# TSAR_Actuator_Controller.net
KiCad netlist of a schematic drawn in EAGLE
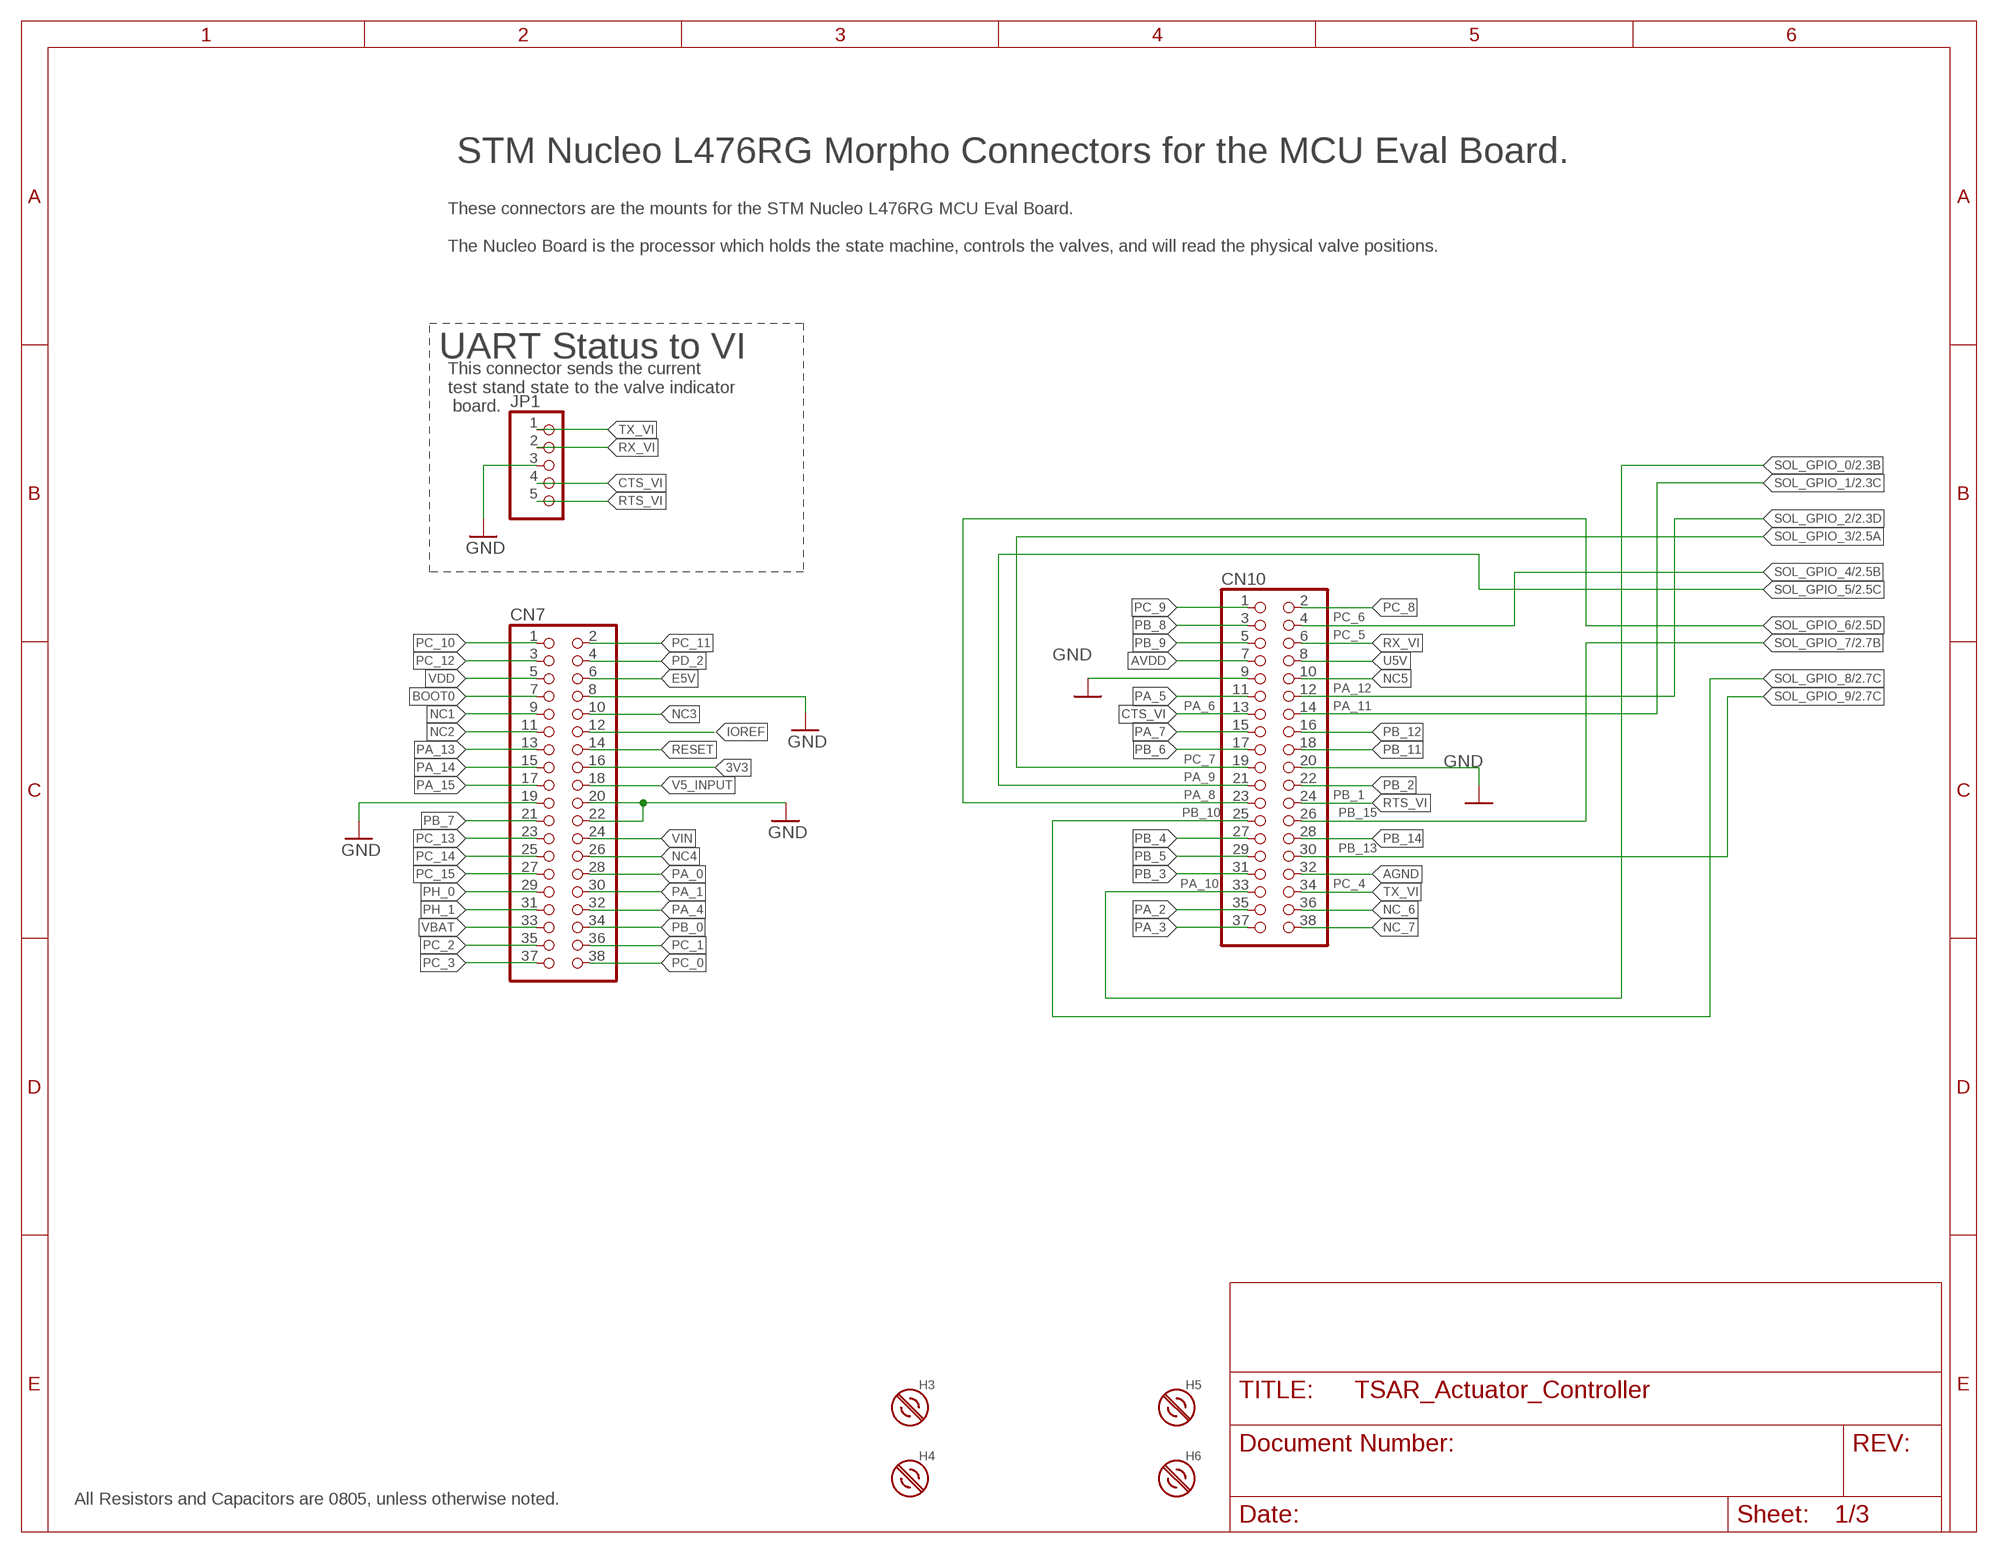
[diagram p0: schematic, sheet 1]
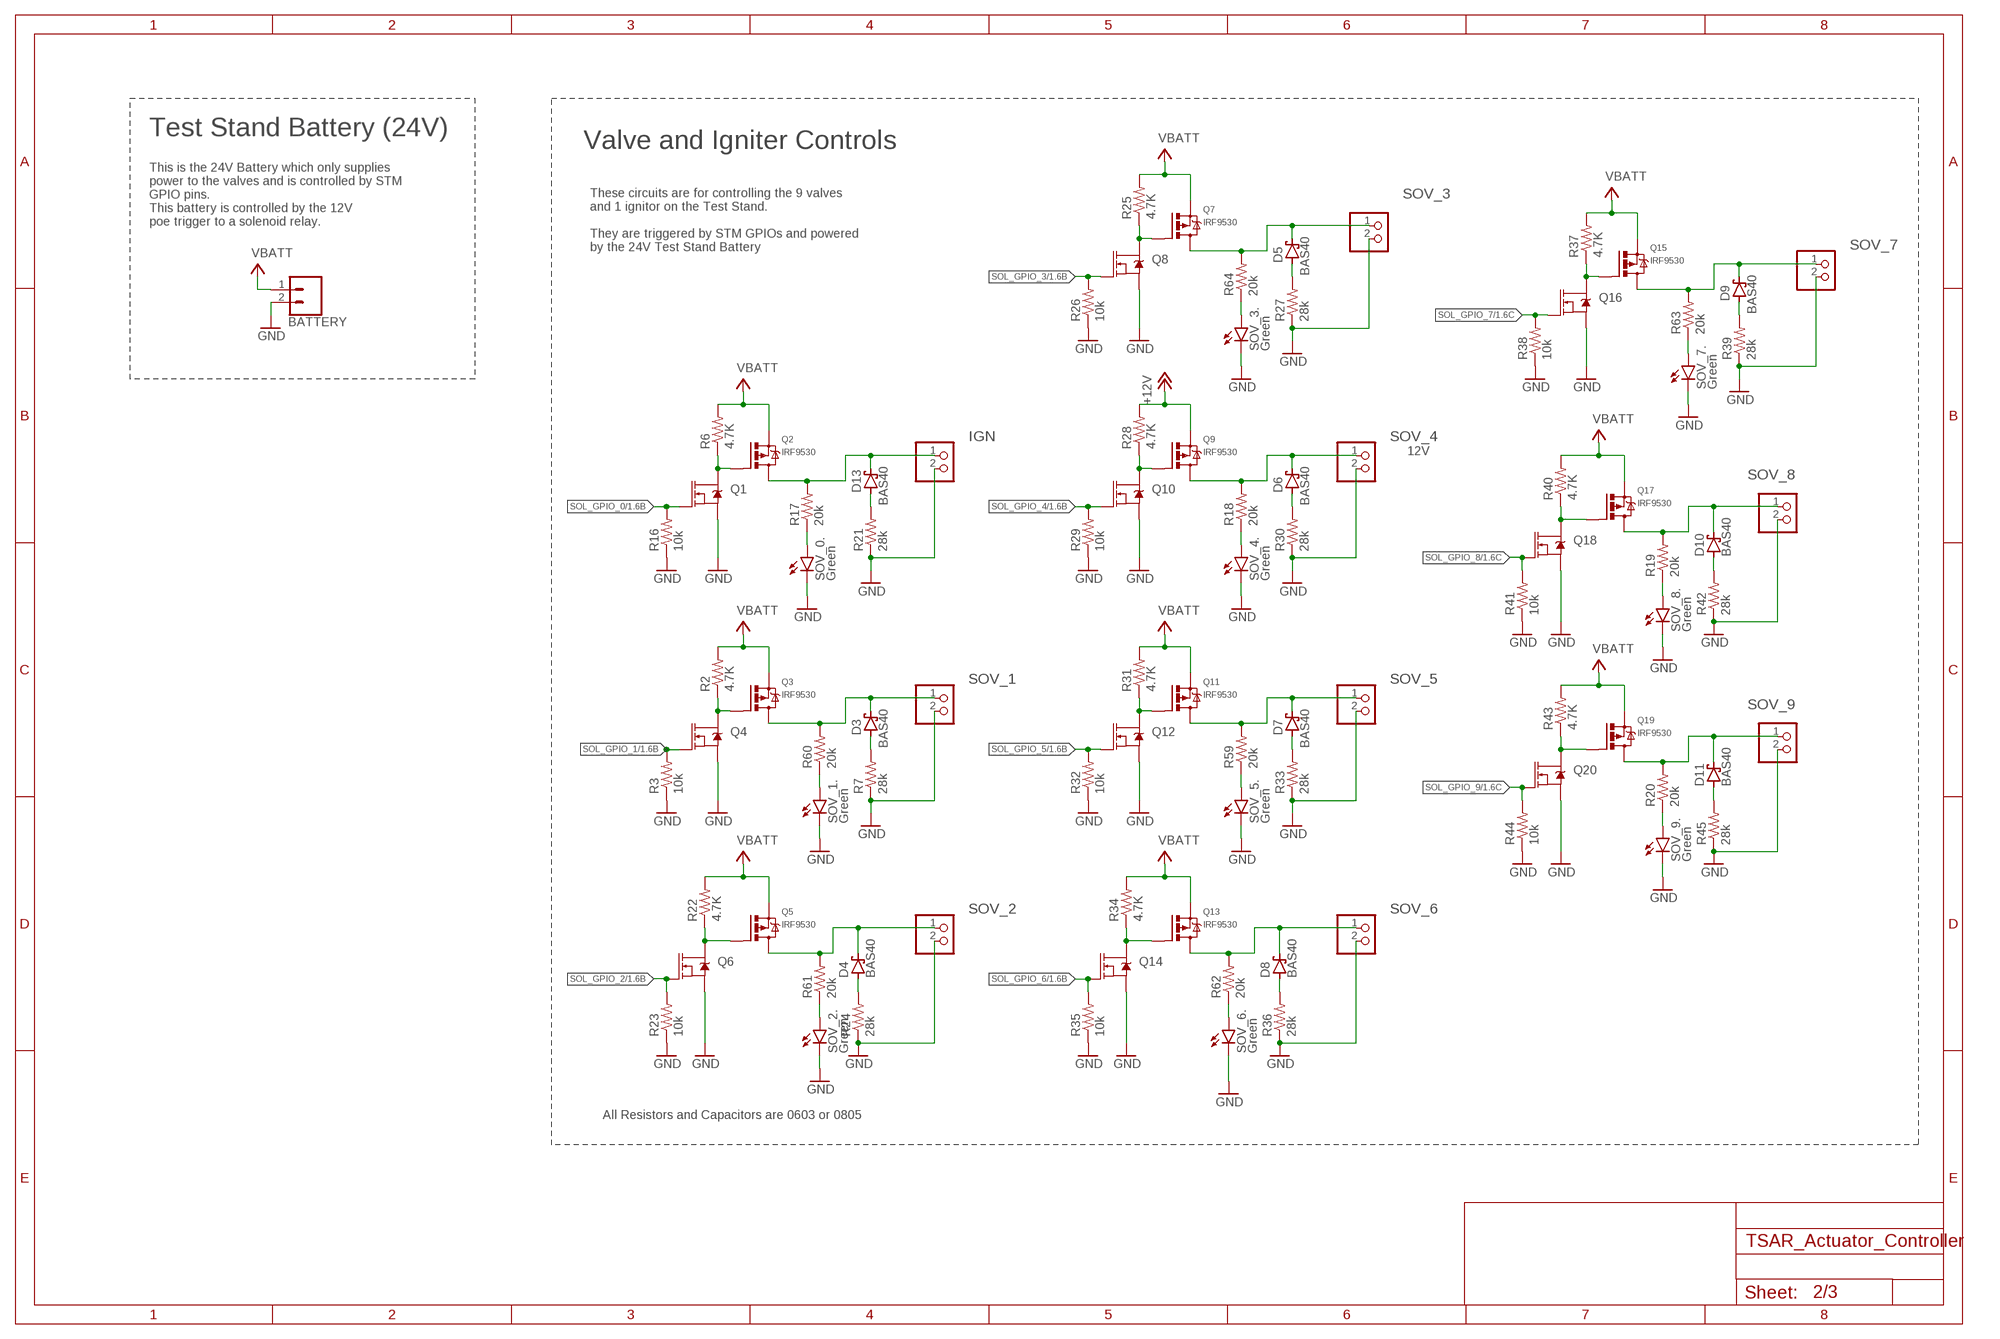
[diagram p1: schematic, sheet 2]
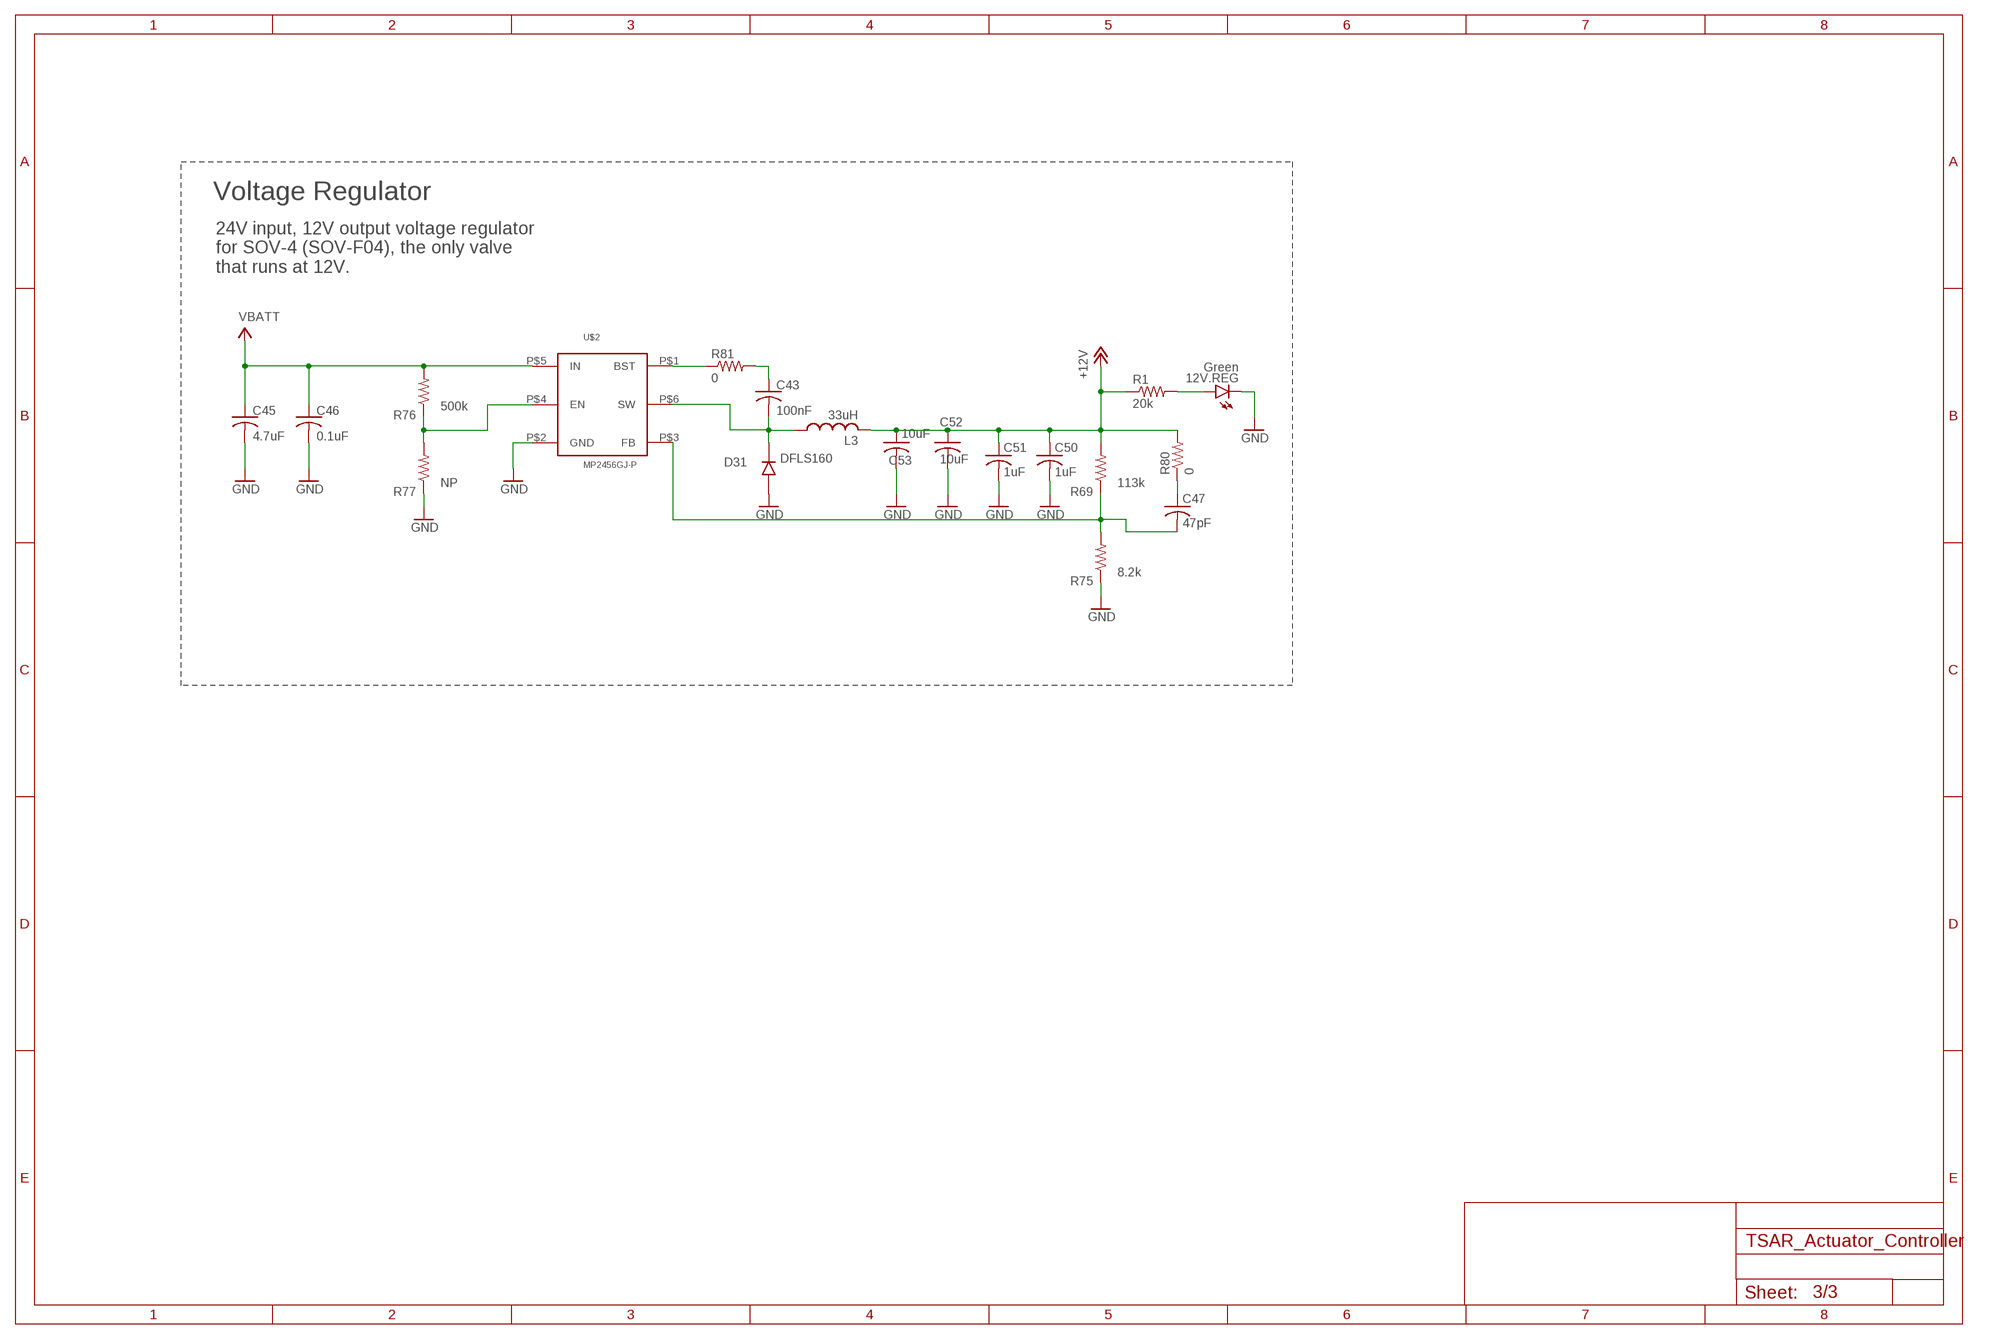
[diagram p2: schematic, sheet 3]

(export (version "E")
  (design (tool "Eeschema 10.0.6"))
  (components
    (comp (ref "12V.REG")
      (value "Green")
      (footprint "eagle-import:CHIP-LED0603")
      (fields (field (name "MFR") "Dialight") (field (name "MPN") "5988070107F"))
      (libsource (lib "eagle-import") (part "LEDCHIP-LED0603"))
    )
    (comp (ref "C43")
      (value "100nF")
      (footprint "eagle-import:C0603K")
      (fields (field (name "MFR") "Samsung Electro-Mechanics") (field (name "MPN") "CL10B104KB8NNNL"))
      (libsource (lib "eagle-import") (part "C-USC0603K"))
    )
    (comp (ref "C45")
      (value "4.7uF")
      (footprint "eagle-import:C0805K")
      (fields (field (name "MFR") "Samsung Electro-Mechanics") (field (name "MPN") "CL21A475KBQNNNE"))
      (libsource (lib "eagle-import") (part "C-USC0805K"))
    )
    (comp (ref "C46")
      (value "0.1uF")
      (footprint "eagle-import:C0603K")
      (fields (field (name "MFR") "Samsung Electro-Mechanics") (field (name "MPN") "CL10B104KB8NNNL"))
      (libsource (lib "eagle-import") (part "C-USC0603K"))
    )
    (comp (ref "C47")
      (value "47pF")
      (footprint "eagle-import:C0603K")
      (fields (field (name "MFR") "TDK Corporation") (field (name "MPN") "C1608C0G1H470J080AA"))
      (libsource (lib "eagle-import") (part "C-USC0603K"))
    )
    (comp (ref "C50")
      (value "1uF")
      (footprint "eagle-import:C0603K")
      (fields (field (name "MFR") "Samsung Electro-Mechanics") (field (name "MPN") "CL10A105KB8NNNC"))
      (libsource (lib "eagle-import") (part "C-USC0603K"))
    )
    (comp (ref "C51")
      (value "1uF")
      (footprint "eagle-import:C0603K")
      (fields (field (name "MFR") "Samsung Electro-Mechanics") (field (name "MPN") "CL10A105KB8NNNC"))
      (libsource (lib "eagle-import") (part "C-USC0603K"))
    )
    (comp (ref "C52")
      (value "10uF")
      (footprint "eagle-import:C1206K")
      (fields (field (name "MFR") "Samsung Electro-Mechanics") (field (name "MPN") "CL31A106MBHNNNE"))
      (libsource (lib "eagle-import") (part "C-USC1206K"))
    )
    (comp (ref "C53")
      (value "10uF")
      (footprint "eagle-import:C1206K")
      (fields (field (name "MFR") "Samsung Electro-Mechanics") (field (name "MPN") "CL31A106MBHNNNE"))
      (libsource (lib "eagle-import") (part "C-USC1206K"))
    )
    (comp (ref "D31")
      (value "DFLS160")
      (footprint "eagle-import:POWERDI-123")
      (fields
        (field (name "DIGI-KEY_PART_NUMBER") "DFLS160DICT-ND")
        (field (name "MF") "Diodes Inc.")
        (field (name "MP") "DFLS160-7")
      )
      (libsource (lib "eagle-import") (part "DFLS160-7"))
    )
    (comp (ref "L3")
      (value "33uH")
      (footprint "eagle-import:0.209_LX0.197_W(5.30MMX5.00MM)")
      (fields (field (name "MFR") "Pulse Electronics Power") (field (name "MPN") "PM4340.333NLT"))
      (libsource (lib "eagle-import") (part "CLF5030NIT-100M-D"))
    )
    (comp (ref "R1")
      (value "20k")
      (footprint "eagle-import:.0603-A-NOSILK")
      (fields (field (name "MFR") "Panasonic Electronic Components") (field (name "MPN") "ERJ-PA3J203V"))
      (libsource (lib "eagle-import") (part "R-US_0603-A-NOSILK"))
    )
    (comp (ref "R69")
      (value "113k")
      (footprint "eagle-import:.0805-A-NOSILK")
      (fields (field (name "MFR") "KOA Speer Electronics, Inc.") (field (name "MPN") "RK73H2ATTD1133F"))
      (libsource (lib "eagle-import") (part "R-US_0805-A-NOSILK"))
    )
    (comp (ref "R75")
      (value "8.2k")
      (footprint "eagle-import:.0805-A-NOSILK")
      (fields (field (name "MFR") "KOA Speer Electronics, Inc.") (field (name "MPN") "RK73H2ATTD8201F"))
      (libsource (lib "eagle-import") (part "R-US_0805-A-NOSILK"))
    )
    (comp (ref "R76")
      (value "500k")
      (footprint "eagle-import:1206-A")
      (fields (field (name "MFR") "Vishay Dale") (field (name "MPN") "CRMA1206AF500KFKEF"))
      (libsource (lib "eagle-import") (part "R-US_1206-A"))
    )
    (comp (ref "R77")
      (value "NP")
      (footprint "eagle-import:.0805-A-NOSILK")
      (libsource (lib "eagle-import") (part "R-US_0805-A-NOSILK"))
    )
    (comp (ref "R80")
      (value "0")
      (footprint "eagle-import:.0603-A-NOSILK")
      (fields (field (name "MFR") "Vishay Dale") (field (name "MPN") "RCS06030000Z0EA"))
      (libsource (lib "eagle-import") (part "R-US_0603-A-NOSILK"))
    )
    (comp (ref "R81")
      (value "0")
      (footprint "eagle-import:.0603-A-NOSILK")
      (fields (field (name "MFR") "Vishay Dale") (field (name "MPN") "RCS06030000Z0EA"))
      (libsource (lib "eagle-import") (part "R-US_0603-A-NOSILK"))
    )
    (comp (ref "U$2")
      (value "MP2456GJ-P")
      (footprint "eagle-import:SOT6")
      (fields (field (name "MFR") "Monolithic Power Systems Inc."))
      (libsource (lib "eagle-import") (part "MP2456GJ-P"))
    )
    (comp (ref "CN7")
      (value "PINHD-2X19")
      (footprint "eagle-import:2X19")
      (fields (field (name "MFR") "Sullins Connector Solutions") (field (name "MPN") "PPPC192LFBN-RC"))
      (libsource (lib "eagle-import") (part "PINHD-2X19"))
    )
    (comp (ref "CN10")
      (value "PINHD-2X19")
      (footprint "eagle-import:2X19")
      (fields (field (name "MFR") "Sullins Connector Solutions") (field (name "MPN") "PPPC192LFBN-RC"))
      (libsource (lib "eagle-import") (part "PINHD-2X19"))
    )
    (comp (ref "H3")
      (value "#4-BARE_MOUNTING_HOLE/.300")
      (footprint "eagle-import:#4_.300-BARE+STD_NUT_OR_STAR_WASHER")
      (libsource (lib "eagle-import") (part "#4-BARE_MOUNTING_HOLE/.300"))
    )
    (comp (ref "H4")
      (value "#4-BARE_MOUNTING_HOLE/.300")
      (footprint "eagle-import:#4_.300-BARE+STD_NUT_OR_STAR_WASHER")
      (libsource (lib "eagle-import") (part "#4-BARE_MOUNTING_HOLE/.300"))
    )
    (comp (ref "H5")
      (value "#4-BARE_MOUNTING_HOLE/.300")
      (footprint "eagle-import:#4_.300-BARE+STD_NUT_OR_STAR_WASHER")
      (libsource (lib "eagle-import") (part "#4-BARE_MOUNTING_HOLE/.300"))
    )
    (comp (ref "H6")
      (value "#4-BARE_MOUNTING_HOLE/.300")
      (footprint "eagle-import:#4_.300-BARE+STD_NUT_OR_STAR_WASHER")
      (libsource (lib "eagle-import") (part "#4-BARE_MOUNTING_HOLE/.300"))
    )
    (comp (ref "JP1")
      (value "PINHD-1X5")
      (footprint "eagle-import:1X05")
      (fields (field (name "MFR") "Molex") (field (name "MPN") "AWHW 10A-0202-T"))
      (libsource (lib "eagle-import") (part "PINHD-1X5"))
    )
    (comp (ref "BATTERY")
      (value "CONN_02PTH4")
      (footprint "eagle-import:1X02_XTRA_BIG")
      (fields (field (name "MFR") "TE Connectivity AMP Connectors") (field (name "MPN") "282837-2"))
      (libsource (lib "eagle-import") (part "CONN_02PTH4"))
    )
    (comp (ref "D3")
      (value "BAS40")
      (footprint "eagle-import:SOT23")
      (fields (field (name "MFR") "Central Semiconductor Corp") (field (name "MPN") "CMPSH1-4 TR PBFREE"))
      (libsource (lib "eagle-import") (part "BAS40"))
    )
    (comp (ref "D4")
      (value "BAS40")
      (footprint "eagle-import:SOT23")
      (fields (field (name "MFR") "Central Semiconductor Corp") (field (name "MPN") "CMPSH1-4 TR PBFREE"))
      (libsource (lib "eagle-import") (part "BAS40"))
    )
    (comp (ref "D5")
      (value "BAS40")
      (footprint "eagle-import:SOT23")
      (fields (field (name "MFR") "Central Semiconductor Corp") (field (name "MPN") "CMPSH1-4 TR PBFREE"))
      (libsource (lib "eagle-import") (part "BAS40"))
    )
    (comp (ref "D6")
      (value "BAS40")
      (footprint "eagle-import:SOT23")
      (fields (field (name "MFR") "Central Semiconductor Corp") (field (name "MPN") "CMPSH1-4 TR PBFREE"))
      (libsource (lib "eagle-import") (part "BAS40"))
    )
    (comp (ref "D7")
      (value "BAS40")
      (footprint "eagle-import:SOT23")
      (fields (field (name "MFR") "Central Semiconductor Corp") (field (name "MPN") "CMPSH1-4 TR PBFREE"))
      (libsource (lib "eagle-import") (part "BAS40"))
    )
    (comp (ref "D8")
      (value "BAS40")
      (footprint "eagle-import:SOT23")
      (fields (field (name "MFR") "Central Semiconductor Corp") (field (name "MPN") "CMPSH1-4 TR PBFREE"))
      (libsource (lib "eagle-import") (part "BAS40"))
    )
    (comp (ref "D9")
      (value "BAS40")
      (footprint "eagle-import:SOT23")
      (fields (field (name "MFR") "Central Semiconductor Corp") (field (name "MPN") "CMPSH1-4 TR PBFREE"))
      (libsource (lib "eagle-import") (part "BAS40"))
    )
    (comp (ref "D10")
      (value "BAS40")
      (footprint "eagle-import:SOT23")
      (fields (field (name "MFR") "Central Semiconductor Corp") (field (name "MPN") "CMPSH1-4 TR PBFREE"))
      (libsource (lib "eagle-import") (part "BAS40"))
    )
    (comp (ref "D11")
      (value "BAS40")
      (footprint "eagle-import:SOT23")
      (fields (field (name "MFR") "Central Semiconductor Corp") (field (name "MPN") "CMPSH1-4 TR PBFREE"))
      (libsource (lib "eagle-import") (part "BAS40"))
    )
    (comp (ref "D13")
      (value "BAS40")
      (footprint "eagle-import:SOT23")
      (fields (field (name "MFR") "Central Semiconductor Corp") (field (name "MPN") "CMPSH1-4 TR PBFREE"))
      (libsource (lib "eagle-import") (part "BAS40"))
    )
    (comp (ref "IGN")
      (value "PINHD-1X2")
      (footprint "eagle-import:1X02")
      (fields (field (name "MFR") "Molex") (field (name "MPN") "0022232021"))
      (libsource (lib "eagle-import") (part "PINHD-1X2"))
    )
    (comp (ref "Q1")
      (value "220mA/50V/3.5Ω")
      (footprint "eagle-import:SOT23-3")
      (fields (field (name "MFR") "Nexperia USA Inc.") (field (name "MPN") "BSS138P,215"))
      (libsource (lib "eagle-import") (part "MOSFET-NCH-BSS138"))
    )
    (comp (ref "Q2")
      (value "IRF9530")
      (footprint "eagle-import:TO220BV")
      (fields (field (name "MFR") "Infineon Technologies") (field (name "MPN") "IRF9530NPBF"))
      (libsource (lib "eagle-import") (part "IRF9530"))
    )
    (comp (ref "Q3")
      (value "IRF9530")
      (footprint "eagle-import:TO220BV")
      (fields (field (name "MFR") "Infineon Technologies") (field (name "MPN") "IRF9530NPBF"))
      (libsource (lib "eagle-import") (part "IRF9530"))
    )
    (comp (ref "Q4")
      (value "220mA/50V/3.5Ω")
      (footprint "eagle-import:SOT23-3")
      (fields (field (name "MFR") "Nexperia USA Inc.") (field (name "MPN") "BSS138P,215"))
      (libsource (lib "eagle-import") (part "MOSFET-NCH-BSS138"))
    )
    (comp (ref "Q5")
      (value "IRF9530")
      (footprint "eagle-import:TO220BV")
      (fields (field (name "MFR") "Infineon Technologies") (field (name "MPN") "IRF9530NPBF"))
      (libsource (lib "eagle-import") (part "IRF9530"))
    )
    (comp (ref "Q6")
      (value "220mA/50V/3.5Ω")
      (footprint "eagle-import:SOT23-3")
      (fields (field (name "MFR") "Nexperia USA Inc.") (field (name "MPN") "BSS138P,215"))
      (libsource (lib "eagle-import") (part "MOSFET-NCH-BSS138"))
    )
    (comp (ref "Q7")
      (value "IRF9530")
      (footprint "eagle-import:TO220BV")
      (fields (field (name "MFR") "Infineon Technologies") (field (name "MPN") "IRF9530NPBF"))
      (libsource (lib "eagle-import") (part "IRF9530"))
    )
    (comp (ref "Q8")
      (value "220mA/50V/3.5Ω")
      (footprint "eagle-import:SOT23-3")
      (fields (field (name "MFR") "Nexperia USA Inc.") (field (name "MPN") "BSS138P,215"))
      (libsource (lib "eagle-import") (part "MOSFET-NCH-BSS138"))
    )
    (comp (ref "Q9")
      (value "IRF9530")
      (footprint "eagle-import:TO220BV")
      (fields (field (name "MFR") "Infineon Technologies") (field (name "MPN") "IRF9530NPBF"))
      (libsource (lib "eagle-import") (part "IRF9530"))
    )
    (comp (ref "Q10")
      (value "220mA/50V/3.5Ω")
      (footprint "eagle-import:SOT23-3")
      (fields (field (name "MFR") "Nexperia USA Inc.") (field (name "MPN") "BSS138P,215"))
      (libsource (lib "eagle-import") (part "MOSFET-NCH-BSS138"))
    )
    (comp (ref "Q11")
      (value "IRF9530")
      (footprint "eagle-import:TO220BV")
      (fields (field (name "MFR") "Infineon Technologies") (field (name "MPN") "IRF9530NPBF"))
      (libsource (lib "eagle-import") (part "IRF9530"))
    )
    (comp (ref "Q12")
      (value "220mA/50V/3.5Ω")
      (footprint "eagle-import:SOT23-3")
      (fields (field (name "MFR") "Nexperia USA Inc.") (field (name "MPN") "BSS138P,215"))
      (libsource (lib "eagle-import") (part "MOSFET-NCH-BSS138"))
    )
    (comp (ref "Q13")
      (value "IRF9530")
      (footprint "eagle-import:TO220BV")
      (fields (field (name "MFR") "Infineon Technologies") (field (name "MPN") "IRF9530NPBF"))
      (libsource (lib "eagle-import") (part "IRF9530"))
    )
    (comp (ref "Q14")
      (value "220mA/50V/3.5Ω")
      (footprint "eagle-import:SOT23-3")
      (fields (field (name "MFR") "Nexperia USA Inc.") (field (name "MPN") "BSS138P,215"))
      (libsource (lib "eagle-import") (part "MOSFET-NCH-BSS138"))
    )
    (comp (ref "Q15")
      (value "IRF9530")
      (footprint "eagle-import:TO220BV")
      (fields (field (name "MFR") "Infineon Technologies") (field (name "MPN") "IRF9530NPBF"))
      (libsource (lib "eagle-import") (part "IRF9530"))
    )
    (comp (ref "Q16")
      (value "220mA/50V/3.5Ω")
      (footprint "eagle-import:SOT23-3")
      (fields (field (name "MFR") "Nexperia USA Inc.") (field (name "MPN") "BSS138P,215"))
      (libsource (lib "eagle-import") (part "MOSFET-NCH-BSS138"))
    )
    (comp (ref "Q17")
      (value "IRF9530")
      (footprint "eagle-import:TO220BV")
      (fields (field (name "MFR") "Infineon Technologies") (field (name "MPN") "IRF9530NPBF"))
      (libsource (lib "eagle-import") (part "IRF9530"))
    )
    (comp (ref "Q18")
      (value "220mA/50V/3.5Ω")
      (footprint "eagle-import:SOT23-3")
      (fields (field (name "MFR") "Nexperia USA Inc.") (field (name "MPN") "BSS138P,215"))
      (libsource (lib "eagle-import") (part "MOSFET-NCH-BSS138"))
    )
    (comp (ref "Q19")
      (value "IRF9530")
      (footprint "eagle-import:TO220BV")
      (fields (field (name "MFR") "Infineon Technologies") (field (name "MPN") "IRF9530NPBF"))
      (libsource (lib "eagle-import") (part "IRF9530"))
    )
    (comp (ref "Q20")
      (value "220mA/50V/3.5Ω")
      (footprint "eagle-import:SOT23-3")
      (fields (field (name "MFR") "Nexperia USA Inc.") (field (name "MPN") "BSS138P,215"))
      (libsource (lib "eagle-import") (part "MOSFET-NCH-BSS138"))
    )
    (comp (ref "R2")
      (value "4.7K")
      (footprint "eagle-import:.0805-A-NOSILK")
      (fields (field (name "MFR") "Yageo") (field (name "MPN") "RC0805FR-074K7L"))
      (libsource (lib "eagle-import") (part "R-US_0805-A-NOSILK"))
    )
    (comp (ref "R3")
      (value "10k")
      (footprint "eagle-import:.0805-A-NOSILK")
      (fields (field (name "MFR") "Yageo") (field (name "MPN") "RC0805FR-0710KL"))
      (libsource (lib "eagle-import") (part "R-US_0805-A-NOSILK"))
    )
    (comp (ref "R6")
      (value "4.7K")
      (footprint "eagle-import:.0805-A-NOSILK")
      (fields (field (name "MFR") "Yageo") (field (name "MPN") "RC0805FR-074K7L"))
      (libsource (lib "eagle-import") (part "R-US_0805-A-NOSILK"))
    )
    (comp (ref "R7")
      (value "28k")
      (footprint "eagle-import:.0805-A-NOSILK")
      (fields (field (name "MFR") "Stackpole Electronics Inc") (field (name "MPN") "RMCF0805FT28K0"))
      (libsource (lib "eagle-import") (part "R-US_0805-A-NOSILK"))
    )
    (comp (ref "R16")
      (value "10k")
      (footprint "eagle-import:.0805-A-NOSILK")
      (fields (field (name "MFR") "Yageo") (field (name "MPN") "RC0805FR-0710KL"))
      (libsource (lib "eagle-import") (part "R-US_0805-A-NOSILK"))
    )
    (comp (ref "R17")
      (value "20k")
      (footprint "eagle-import:.0603-A-NOSILK")
      (fields (field (name "MFR") "Rohm Semiconductor") (field (name "MPN") "ESR03EZPJ203"))
      (libsource (lib "eagle-import") (part "R-US_0603-A-NOSILK"))
    )
    (comp (ref "R18")
      (value "20k")
      (footprint "eagle-import:.0603-A-NOSILK")
      (fields (field (name "MFR") "Rohm Semiconductor") (field (name "MPN") "ESR03EZPJ203"))
      (libsource (lib "eagle-import") (part "R-US_0603-A-NOSILK"))
    )
    (comp (ref "R19")
      (value "20k")
      (footprint "eagle-import:.0603-A-NOSILK")
      (fields (field (name "MFR") "Rohm Semiconductor") (field (name "MPN") "ESR03EZPJ203"))
      (libsource (lib "eagle-import") (part "R-US_0603-A-NOSILK"))
    )
    (comp (ref "R20")
      (value "20k")
      (footprint "eagle-import:.0603-A-NOSILK")
      (fields (field (name "MFR") "Rohm Semiconductor") (field (name "MPN") "ESR03EZPJ203"))
      (libsource (lib "eagle-import") (part "R-US_0603-A-NOSILK"))
    )
    (comp (ref "R21")
      (value "28k")
      (footprint "eagle-import:.0805-A-NOSILK")
      (fields (field (name "MFR") "Stackpole Electronics Inc") (field (name "MPN") "RMCF0805FT28K0"))
      (libsource (lib "eagle-import") (part "R-US_0805-A-NOSILK"))
    )
    (comp (ref "R22")
      (value "4.7K")
      (footprint "eagle-import:.0805-A-NOSILK")
      (fields (field (name "MFR") "Yageo") (field (name "MPN") "RC0805FR-074K7L"))
      (libsource (lib "eagle-import") (part "R-US_0805-A-NOSILK"))
    )
    (comp (ref "R23")
      (value "10k")
      (footprint "eagle-import:.0805-A-NOSILK")
      (fields (field (name "MFR") "Yageo") (field (name "MPN") "RC0805FR-0710KL"))
      (libsource (lib "eagle-import") (part "R-US_0805-A-NOSILK"))
    )
    (comp (ref "R24")
      (value "28k")
      (footprint "eagle-import:.0805-A-NOSILK")
      (fields (field (name "MFR") "Stackpole Electronics Inc") (field (name "MPN") "RMCF0805FT28K0"))
      (libsource (lib "eagle-import") (part "R-US_0805-A-NOSILK"))
    )
    (comp (ref "R25")
      (value "4.7K")
      (footprint "eagle-import:.0805-A-NOSILK")
      (fields (field (name "MFR") "Yageo") (field (name "MPN") "RC0805FR-074K7L"))
      (libsource (lib "eagle-import") (part "R-US_0805-A-NOSILK"))
    )
    (comp (ref "R26")
      (value "10k")
      (footprint "eagle-import:.0805-A-NOSILK")
      (fields (field (name "MFR") "Yageo") (field (name "MPN") "RC0805FR-0710KL"))
      (libsource (lib "eagle-import") (part "R-US_0805-A-NOSILK"))
    )
    (comp (ref "R27")
      (value "28k")
      (footprint "eagle-import:.0805-A-NOSILK")
      (fields (field (name "MFR") "Stackpole Electronics Inc") (field (name "MPN") "RMCF0805FT28K0"))
      (libsource (lib "eagle-import") (part "R-US_0805-A-NOSILK"))
    )
    (comp (ref "R28")
      (value "4.7K")
      (footprint "eagle-import:.0805-A-NOSILK")
      (fields (field (name "MFR") "Yageo") (field (name "MPN") "RC0805FR-074K7L"))
      (libsource (lib "eagle-import") (part "R-US_0805-A-NOSILK"))
    )
    (comp (ref "R29")
      (value "10k")
      (footprint "eagle-import:.0805-A-NOSILK")
      (fields (field (name "MFR") "Yageo") (field (name "MPN") "RC0805FR-0710KL"))
      (libsource (lib "eagle-import") (part "R-US_0805-A-NOSILK"))
    )
    (comp (ref "R30")
      (value "28k")
      (footprint "eagle-import:.0805-A-NOSILK")
      (fields (field (name "MFR") "Stackpole Electronics Inc") (field (name "MPN") "RMCF0805FT28K0"))
      (libsource (lib "eagle-import") (part "R-US_0805-A-NOSILK"))
    )
    (comp (ref "R31")
      (value "4.7K")
      (footprint "eagle-import:.0805-A-NOSILK")
      (fields (field (name "MFR") "Yageo") (field (name "MPN") "RC0805FR-074K7L"))
      (libsource (lib "eagle-import") (part "R-US_0805-A-NOSILK"))
    )
    (comp (ref "R32")
      (value "10k")
      (footprint "eagle-import:.0805-A-NOSILK")
      (fields (field (name "MFR") "Yageo") (field (name "MPN") "RC0805FR-0710KL"))
      (libsource (lib "eagle-import") (part "R-US_0805-A-NOSILK"))
    )
    (comp (ref "R33")
      (value "28k")
      (footprint "eagle-import:.0805-A-NOSILK")
      (fields (field (name "MFR") "Stackpole Electronics Inc") (field (name "MPN") "RMCF0805FT28K0"))
      (libsource (lib "eagle-import") (part "R-US_0805-A-NOSILK"))
    )
    (comp (ref "R34")
      (value "4.7K")
      (footprint "eagle-import:.0805-A-NOSILK")
      (fields (field (name "MFR") "Yageo") (field (name "MPN") "RC0805FR-074K7L"))
      (libsource (lib "eagle-import") (part "R-US_0805-A-NOSILK"))
    )
    (comp (ref "R35")
      (value "10k")
      (footprint "eagle-import:.0805-A-NOSILK")
      (fields (field (name "MFR") "Yageo") (field (name "MPN") "RC0805FR-0710KL"))
      (libsource (lib "eagle-import") (part "R-US_0805-A-NOSILK"))
    )
    (comp (ref "R36")
      (value "28k")
      (footprint "eagle-import:.0805-A-NOSILK")
      (fields (field (name "MFR") "Stackpole Electronics Inc") (field (name "MPN") "RMCF0805FT28K0"))
      (libsource (lib "eagle-import") (part "R-US_0805-A-NOSILK"))
    )
    (comp (ref "R37")
      (value "4.7K")
      (footprint "eagle-import:.0805-A-NOSILK")
      (fields (field (name "MFR") "Yageo") (field (name "MPN") "RC0805FR-074K7L"))
      (libsource (lib "eagle-import") (part "R-US_0805-A-NOSILK"))
    )
    (comp (ref "R38")
      (value "10k")
      (footprint "eagle-import:.0805-A-NOSILK")
      (fields (field (name "MFR") "Yageo") (field (name "MPN") "RC0805FR-0710KL"))
      (libsource (lib "eagle-import") (part "R-US_0805-A-NOSILK"))
    )
    (comp (ref "R39")
      (value "28k")
      (footprint "eagle-import:.0805-A-NOSILK")
      (fields (field (name "MFR") "Stackpole Electronics Inc") (field (name "MPN") "RMCF0805FT28K0"))
      (libsource (lib "eagle-import") (part "R-US_0805-A-NOSILK"))
    )
    (comp (ref "R40")
      (value "4.7K")
      (footprint "eagle-import:.0805-A-NOSILK")
      (fields (field (name "MFR") "Yageo") (field (name "MPN") "RC0805FR-074K7L"))
      (libsource (lib "eagle-import") (part "R-US_0805-A-NOSILK"))
    )
    (comp (ref "R41")
      (value "10k")
      (footprint "eagle-import:.0805-A-NOSILK")
      (fields (field (name "MFR") "Yageo") (field (name "MPN") "RC0805FR-0710KL"))
      (libsource (lib "eagle-import") (part "R-US_0805-A-NOSILK"))
    )
    (comp (ref "R42")
      (value "28k")
      (footprint "eagle-import:.0805-A-NOSILK")
      (fields (field (name "MFR") "Stackpole Electronics Inc") (field (name "MPN") "RMCF0805FT28K0"))
      (libsource (lib "eagle-import") (part "R-US_0805-A-NOSILK"))
    )
    (comp (ref "R43")
      (value "4.7K")
      (footprint "eagle-import:.0805-A-NOSILK")
      (fields (field (name "MFR") "Yageo") (field (name "MPN") "RC0805FR-074K7L"))
      (libsource (lib "eagle-import") (part "R-US_0805-A-NOSILK"))
    )
    (comp (ref "R44")
      (value "10k")
      (footprint "eagle-import:.0805-A-NOSILK")
      (fields (field (name "MFR") "Yageo") (field (name "MPN") "RC0805FR-0710KL"))
      (libsource (lib "eagle-import") (part "R-US_0805-A-NOSILK"))
    )
    (comp (ref "R45")
      (value "28k")
      (footprint "eagle-import:.0805-A-NOSILK")
      (fields (field (name "MFR") "Stackpole Electronics Inc") (field (name "MPN") "RMCF0805FT28K0"))
      (libsource (lib "eagle-import") (part "R-US_0805-A-NOSILK"))
    )
    (comp (ref "R59")
      (value "20k")
      (footprint "eagle-import:.0603-A-NOSILK")
      (fields (field (name "MFR") "Rohm Semiconductor") (field (name "MPN") "ESR03EZPJ203"))
      (libsource (lib "eagle-import") (part "R-US_0603-A-NOSILK"))
    )
    (comp (ref "R60")
      (value "20k")
      (footprint "eagle-import:.0603-A-NOSILK")
      (fields (field (name "MFR") "Rohm Semiconductor") (field (name "MPN") "ESR03EZPJ203"))
      (libsource (lib "eagle-import") (part "R-US_0603-A-NOSILK"))
    )
    (comp (ref "R61")
      (value "20k")
      (footprint "eagle-import:.0603-A-NOSILK")
      (fields (field (name "MFR") "Rohm Semiconductor") (field (name "MPN") "ESR03EZPJ203"))
      (libsource (lib "eagle-import") (part "R-US_0603-A-NOSILK"))
    )
    (comp (ref "R62")
      (value "20k")
      (footprint "eagle-import:.0603-A-NOSILK")
      (fields (field (name "MFR") "Rohm Semiconductor") (field (name "MPN") "ESR03EZPJ203"))
      (libsource (lib "eagle-import") (part "R-US_0603-A-NOSILK"))
    )
    (comp (ref "R63")
      (value "20k")
      (footprint "eagle-import:.0603-A-NOSILK")
      (fields (field (name "MFR") "Rohm Semiconductor") (field (name "MPN") "ESR03EZPJ203"))
      (libsource (lib "eagle-import") (part "R-US_0603-A-NOSILK"))
    )
    (comp (ref "R64")
      (value "20k")
      (footprint "eagle-import:.0603-A-NOSILK")
      (fields (field (name "MFR") "Rohm Semiconductor") (field (name "MPN") "ESR03EZPJ203"))
      (libsource (lib "eagle-import") (part "R-US_0603-A-NOSILK"))
    )
    (comp (ref "SOV_0.")
      (value "Green")
      (footprint "eagle-import:CHIP-LED0603")
      (fields (field (name "MFR") "Dialight") (field (name "MPN") "5988070107F"))
      (libsource (lib "eagle-import") (part "LEDCHIP-LED0603"))
    )
    (comp (ref "SOV_1")
      (value "PINHD-1X2")
      (footprint "eagle-import:1X02")
      (fields (field (name "MFR") "Molex") (field (name "MPN") "0022232021"))
      (libsource (lib "eagle-import") (part "PINHD-1X2"))
    )
    (comp (ref "SOV_1.")
      (value "Green")
      (footprint "eagle-import:CHIP-LED0603")
      (fields (field (name "MFR") "Dialight") (field (name "MPN") "5988070107F"))
      (libsource (lib "eagle-import") (part "LEDCHIP-LED0603"))
    )
    (comp (ref "SOV_2")
      (value "PINHD-1X2")
      (footprint "eagle-import:1X02")
      (fields (field (name "MFR") "Molex") (field (name "MPN") "0022232021"))
      (libsource (lib "eagle-import") (part "PINHD-1X2"))
    )
    (comp (ref "SOV_2.")
      (value "Green")
      (footprint "eagle-import:CHIP-LED0603")
      (fields (field (name "MFR") "Dialight") (field (name "MPN") "5988070107F"))
      (libsource (lib "eagle-import") (part "LEDCHIP-LED0603"))
    )
    (comp (ref "SOV_3")
      (value "PINHD-1X2")
      (footprint "eagle-import:1X02")
      (fields (field (name "MFR") "Molex") (field (name "MPN") "0022232021"))
      (libsource (lib "eagle-import") (part "PINHD-1X2"))
    )
    (comp (ref "SOV_3.")
      (value "Green")
      (footprint "eagle-import:CHIP-LED0603")
      (fields (field (name "MFR") "Dialight") (field (name "MPN") "5988070107F"))
      (libsource (lib "eagle-import") (part "LEDCHIP-LED0603"))
    )
    (comp (ref "SOV_4")
      (value "PINHD-1X2")
      (footprint "eagle-import:1X02")
      (fields (field (name "MFR") "Molex") (field (name "MPN") "0022232021"))
      (libsource (lib "eagle-import") (part "PINHD-1X2"))
    )
    (comp (ref "SOV_4.")
      (value "Green")
      (footprint "eagle-import:CHIP-LED0603")
      (fields (field (name "MFR") "Dialight") (field (name "MPN") "5988070107F"))
      (libsource (lib "eagle-import") (part "LEDCHIP-LED0603"))
    )
    (comp (ref "SOV_5")
      (value "PINHD-1X2")
      (footprint "eagle-import:1X02")
      (fields (field (name "MFR") "Molex") (field (name "MPN") "0022232021"))
      (libsource (lib "eagle-import") (part "PINHD-1X2"))
    )
    (comp (ref "SOV_5.")
      (value "Green")
      (footprint "eagle-import:CHIP-LED0603")
      (fields (field (name "MFR") "Dialight") (field (name "MPN") "5988070107F"))
      (libsource (lib "eagle-import") (part "LEDCHIP-LED0603"))
    )
    (comp (ref "SOV_6")
      (value "PINHD-1X2")
      (footprint "eagle-import:1X02")
      (fields (field (name "MFR") "Molex") (field (name "MPN") "0022232021"))
      (libsource (lib "eagle-import") (part "PINHD-1X2"))
    )
    (comp (ref "SOV_6.")
      (value "Green")
      (footprint "eagle-import:CHIP-LED0603")
      (fields (field (name "MFR") "Dialight") (field (name "MPN") "5988070107F"))
      (libsource (lib "eagle-import") (part "LEDCHIP-LED0603"))
    )
    (comp (ref "SOV_7")
      (value "PINHD-1X2")
      (footprint "eagle-import:1X02")
      (fields (field (name "MFR") "Molex") (field (name "MPN") "0022232021"))
      (libsource (lib "eagle-import") (part "PINHD-1X2"))
    )
    (comp (ref "SOV_7.")
      (value "Green")
      (footprint "eagle-import:CHIP-LED0603")
      (fields (field (name "MFR") "Dialight") (field (name "MPN") "5988070107F"))
      (libsource (lib "eagle-import") (part "LEDCHIP-LED0603"))
    )
    (comp (ref "SOV_8")
      (value "PINHD-1X2")
      (footprint "eagle-import:1X02")
      (fields (field (name "MFR") "Molex") (field (name "MPN") "0022232021"))
      (libsource (lib "eagle-import") (part "PINHD-1X2"))
    )
    (comp (ref "SOV_8.")
      (value "Green")
      (footprint "eagle-import:CHIP-LED0603")
      (fields (field (name "MFR") "Dialight") (field (name "MPN") "5988070107F"))
      (libsource (lib "eagle-import") (part "LEDCHIP-LED0603"))
    )
    (comp (ref "SOV_9")
      (value "PINHD-1X2")
      (footprint "eagle-import:1X02")
      (fields (field (name "MFR") "Molex") (field (name "MPN") "0022232021"))
      (libsource (lib "eagle-import") (part "PINHD-1X2"))
    )
    (comp (ref "SOV_9.")
      (value "Green")
      (footprint "eagle-import:CHIP-LED0603")
      (fields (field (name "MFR") "Dialight") (field (name "MPN") "5988070107F"))
      (libsource (lib "eagle-import") (part "LEDCHIP-LED0603"))
    )
  )
  (nets
    (net (code "1") (name "+12V") (class "Default")
      (node (ref "C50") (pin "1") (pinfunction "1_1") (pintype "passive"))
      (node (ref "C51") (pin "1") (pinfunction "1_1") (pintype "passive"))
      (node (ref "C52") (pin "1") (pinfunction "1_1") (pintype "passive"))
      (node (ref "C53") (pin "1") (pinfunction "1_1") (pintype "passive"))
      (node (ref "L3") (pin "2") (pinfunction "2_2") (pintype "passive"))
      (node (ref "Q9") (pin "S") (pinfunction "S_S") (pintype "passive"))
      (node (ref "R1") (pin "1") (pinfunction "1_1") (pintype "passive"))
      (node (ref "R28") (pin "2") (pinfunction "2_2") (pintype "passive"))
      (node (ref "R69") (pin "2") (pinfunction "2_2") (pintype "passive"))
      (node (ref "R80") (pin "2") (pinfunction "2_2") (pintype "passive"))
    )
    (net (code "2") (name "3V3") (class "Default")
      (node (ref "CN7") (pin "16") (pinfunction "16_16") (pintype "passive"))
    )
    (net (code "3") (name "AGND") (class "Default")
      (node (ref "CN10") (pin "32") (pinfunction "32_32") (pintype "passive"))
    )
    (net (code "4") (name "AVDD") (class "Default")
      (node (ref "CN10") (pin "7") (pinfunction "7_7") (pintype "passive"))
    )
    (net (code "5") (name "BOOT0") (class "Default")
      (node (ref "CN7") (pin "7") (pinfunction "7_7") (pintype "passive"))
    )
    (net (code "6") (name "CTS_VI") (class "Default")
      (node (ref "CN10") (pin "13") (pinfunction "13_13") (pintype "passive"))
      (node (ref "JP1") (pin "4") (pinfunction "4_4") (pintype "passive"))
    )
    (net (code "7") (name "E5V") (class "Default")
      (node (ref "CN7") (pin "6") (pinfunction "6_6") (pintype "passive"))
    )
    (net (code "8") (name "GND") (class "Default")
      (node (ref "12V.REG") (pin "C") (pinfunction "C_C") (pintype "passive"))
      (node (ref "BATTERY") (pin "2") (pinfunction "2_2") (pintype "passive"))
      (node (ref "C45") (pin "2") (pinfunction "2_2") (pintype "passive"))
      (node (ref "C46") (pin "2") (pinfunction "2_2") (pintype "passive"))
      (node (ref "C50") (pin "2") (pinfunction "2_2") (pintype "passive"))
      (node (ref "C51") (pin "2") (pinfunction "2_2") (pintype "passive"))
      (node (ref "C52") (pin "2") (pinfunction "2_2") (pintype "passive"))
      (node (ref "C53") (pin "2") (pinfunction "2_2") (pintype "passive"))
      (node (ref "CN10") (pin "20") (pinfunction "20_20") (pintype "passive"))
      (node (ref "CN10") (pin "9") (pinfunction "9_9") (pintype "passive"))
      (node (ref "CN7") (pin "19") (pinfunction "19_19") (pintype "passive"))
      (node (ref "CN7") (pin "20") (pinfunction "20_20") (pintype "passive"))
      (node (ref "CN7") (pin "22") (pinfunction "22_22") (pintype "passive"))
      (node (ref "CN7") (pin "8") (pinfunction "8_8") (pintype "passive"))
      (node (ref "D31") (pin "A") (pinfunction "A_A") (pintype "passive"))
      (node (ref "IGN") (pin "2") (pinfunction "2_2") (pintype "passive"))
      (node (ref "JP1") (pin "3") (pinfunction "3_3") (pintype "passive"))
      (node (ref "Q1") (pin "2") (pinfunction "S_2") (pintype "bidirectional"))
      (node (ref "Q10") (pin "2") (pinfunction "S_2") (pintype "bidirectional"))
      (node (ref "Q12") (pin "2") (pinfunction "S_2") (pintype "bidirectional"))
      (node (ref "Q14") (pin "2") (pinfunction "S_2") (pintype "bidirectional"))
      (node (ref "Q16") (pin "2") (pinfunction "S_2") (pintype "bidirectional"))
      (node (ref "Q18") (pin "2") (pinfunction "S_2") (pintype "bidirectional"))
      (node (ref "Q20") (pin "2") (pinfunction "S_2") (pintype "bidirectional"))
      (node (ref "Q4") (pin "2") (pinfunction "S_2") (pintype "bidirectional"))
      (node (ref "Q6") (pin "2") (pinfunction "S_2") (pintype "bidirectional"))
      (node (ref "Q8") (pin "2") (pinfunction "S_2") (pintype "bidirectional"))
      (node (ref "R16") (pin "1") (pinfunction "1_1") (pintype "passive"))
      (node (ref "R21") (pin "1") (pinfunction "1_1") (pintype "passive"))
      (node (ref "R23") (pin "1") (pinfunction "1_1") (pintype "passive"))
      (node (ref "R24") (pin "1") (pinfunction "1_1") (pintype "passive"))
      (node (ref "R26") (pin "1") (pinfunction "1_1") (pintype "passive"))
      (node (ref "R27") (pin "1") (pinfunction "1_1") (pintype "passive"))
      (node (ref "R29") (pin "1") (pinfunction "1_1") (pintype "passive"))
      (node (ref "R3") (pin "1") (pinfunction "1_1") (pintype "passive"))
      (node (ref "R30") (pin "1") (pinfunction "1_1") (pintype "passive"))
      (node (ref "R32") (pin "1") (pinfunction "1_1") (pintype "passive"))
      (node (ref "R33") (pin "1") (pinfunction "1_1") (pintype "passive"))
      (node (ref "R35") (pin "1") (pinfunction "1_1") (pintype "passive"))
      (node (ref "R36") (pin "1") (pinfunction "1_1") (pintype "passive"))
      (node (ref "R38") (pin "1") (pinfunction "1_1") (pintype "passive"))
      (node (ref "R39") (pin "1") (pinfunction "1_1") (pintype "passive"))
      (node (ref "R41") (pin "1") (pinfunction "1_1") (pintype "passive"))
      (node (ref "R42") (pin "1") (pinfunction "1_1") (pintype "passive"))
      (node (ref "R44") (pin "1") (pinfunction "1_1") (pintype "passive"))
      (node (ref "R45") (pin "1") (pinfunction "1_1") (pintype "passive"))
      (node (ref "R7") (pin "1") (pinfunction "1_1") (pintype "passive"))
      (node (ref "R75") (pin "1") (pinfunction "1_1") (pintype "passive"))
      (node (ref "R77") (pin "1") (pinfunction "1_1") (pintype "passive"))
      (node (ref "SOV_0.") (pin "C") (pinfunction "C_C") (pintype "passive"))
      (node (ref "SOV_1") (pin "2") (pinfunction "2_2") (pintype "passive"))
      (node (ref "SOV_1.") (pin "C") (pinfunction "C_C") (pintype "passive"))
      (node (ref "SOV_2") (pin "2") (pinfunction "2_2") (pintype "passive"))
      (node (ref "SOV_2.") (pin "C") (pinfunction "C_C") (pintype "passive"))
      (node (ref "SOV_3") (pin "2") (pinfunction "2_2") (pintype "passive"))
      (node (ref "SOV_3.") (pin "C") (pinfunction "C_C") (pintype "passive"))
      (node (ref "SOV_4") (pin "2") (pinfunction "2_2") (pintype "passive"))
      (node (ref "SOV_4.") (pin "C") (pinfunction "C_C") (pintype "passive"))
      (node (ref "SOV_5") (pin "2") (pinfunction "2_2") (pintype "passive"))
      (node (ref "SOV_5.") (pin "C") (pinfunction "C_C") (pintype "passive"))
      (node (ref "SOV_6") (pin "2") (pinfunction "2_2") (pintype "passive"))
      (node (ref "SOV_6.") (pin "C") (pinfunction "C_C") (pintype "passive"))
      (node (ref "SOV_7") (pin "2") (pinfunction "2_2") (pintype "passive"))
      (node (ref "SOV_7.") (pin "C") (pinfunction "C_C") (pintype "passive"))
      (node (ref "SOV_8") (pin "2") (pinfunction "2_2") (pintype "passive"))
      (node (ref "SOV_8.") (pin "C") (pinfunction "C_C") (pintype "passive"))
      (node (ref "SOV_9") (pin "2") (pinfunction "2_2") (pintype "passive"))
      (node (ref "SOV_9.") (pin "C") (pinfunction "C_C") (pintype "passive"))
      (node (ref "U$2") (pin "P$2") (pinfunction "GND_P$2") (pintype "bidirectional"))
    )
    (net (code "9") (name "IOREF") (class "Default")
      (node (ref "CN7") (pin "12") (pinfunction "12_12") (pintype "passive"))
    )
    (net (code "10") (name "NC1") (class "Default")
      (node (ref "CN7") (pin "9") (pinfunction "9_9") (pintype "passive"))
    )
    (net (code "11") (name "NC2") (class "Default")
      (node (ref "CN7") (pin "11") (pinfunction "11_11") (pintype "passive"))
    )
    (net (code "12") (name "NC3") (class "Default")
      (node (ref "CN7") (pin "10") (pinfunction "10_10") (pintype "passive"))
    )
    (net (code "13") (name "NC4") (class "Default")
      (node (ref "CN7") (pin "26") (pinfunction "26_26") (pintype "passive"))
    )
    (net (code "14") (name "NC5") (class "Default")
      (node (ref "CN10") (pin "10") (pinfunction "10_10") (pintype "passive"))
    )
    (net (code "15") (name "NC_6") (class "Default")
      (node (ref "CN10") (pin "36") (pinfunction "36_36") (pintype "passive"))
    )
    (net (code "16") (name "NC_7") (class "Default")
      (node (ref "CN10") (pin "38") (pinfunction "38_38") (pintype "passive"))
    )
    (net (code "17") (name "Net-(12V.REG-PadA)") (class "Default")
      (node (ref "12V.REG") (pin "A") (pinfunction "A_A") (pintype "passive"))
      (node (ref "R1") (pin "2") (pinfunction "2_2") (pintype "passive"))
    )
    (net (code "18") (name "Net-(C43-Pad1)") (class "Default")
      (node (ref "C43") (pin "1") (pinfunction "1_1") (pintype "passive"))
      (node (ref "R81") (pin "2") (pinfunction "2_2") (pintype "passive"))
    )
    (net (code "19") (name "Net-(C47-Pad1)") (class "Default")
      (node (ref "C47") (pin "1") (pinfunction "1_1") (pintype "passive"))
      (node (ref "R80") (pin "1") (pinfunction "1_1") (pintype "passive"))
    )
    (net (code "20") (name "Net-(D3-A)") (class "Default")
      (node (ref "D3") (pin "1") (pinfunction "A_1") (pintype "passive"))
      (node (ref "R7") (pin "2") (pinfunction "2_2") (pintype "passive"))
    )
    (net (code "21") (name "Net-(D3-C)") (class "Default")
      (node (ref "D3") (pin "3") (pinfunction "C_3") (pintype "passive"))
      (node (ref "Q3") (pin "D") (pinfunction "D_D") (pintype "passive"))
      (node (ref "R60") (pin "2") (pinfunction "2_2") (pintype "passive"))
      (node (ref "SOV_1") (pin "1") (pinfunction "1_1") (pintype "passive"))
    )
    (net (code "22") (name "Net-(D4-A)") (class "Default")
      (node (ref "D4") (pin "1") (pinfunction "A_1") (pintype "passive"))
      (node (ref "R24") (pin "2") (pinfunction "2_2") (pintype "passive"))
    )
    (net (code "23") (name "Net-(D4-C)") (class "Default")
      (node (ref "D4") (pin "3") (pinfunction "C_3") (pintype "passive"))
      (node (ref "Q5") (pin "D") (pinfunction "D_D") (pintype "passive"))
      (node (ref "R61") (pin "2") (pinfunction "2_2") (pintype "passive"))
      (node (ref "SOV_2") (pin "1") (pinfunction "1_1") (pintype "passive"))
    )
    (net (code "24") (name "Net-(D5-A)") (class "Default")
      (node (ref "D5") (pin "1") (pinfunction "A_1") (pintype "passive"))
      (node (ref "R27") (pin "2") (pinfunction "2_2") (pintype "passive"))
    )
    (net (code "25") (name "Net-(D5-C)") (class "Default")
      (node (ref "D5") (pin "3") (pinfunction "C_3") (pintype "passive"))
      (node (ref "Q7") (pin "D") (pinfunction "D_D") (pintype "passive"))
      (node (ref "R64") (pin "2") (pinfunction "2_2") (pintype "passive"))
      (node (ref "SOV_3") (pin "1") (pinfunction "1_1") (pintype "passive"))
    )
    (net (code "26") (name "Net-(D6-A)") (class "Default")
      (node (ref "D6") (pin "1") (pinfunction "A_1") (pintype "passive"))
      (node (ref "R30") (pin "2") (pinfunction "2_2") (pintype "passive"))
    )
    (net (code "27") (name "Net-(D6-C)") (class "Default")
      (node (ref "D6") (pin "3") (pinfunction "C_3") (pintype "passive"))
      (node (ref "Q9") (pin "D") (pinfunction "D_D") (pintype "passive"))
      (node (ref "R18") (pin "2") (pinfunction "2_2") (pintype "passive"))
      (node (ref "SOV_4") (pin "1") (pinfunction "1_1") (pintype "passive"))
    )
    (net (code "28") (name "Net-(D7-A)") (class "Default")
      (node (ref "D7") (pin "1") (pinfunction "A_1") (pintype "passive"))
      (node (ref "R33") (pin "2") (pinfunction "2_2") (pintype "passive"))
    )
    (net (code "29") (name "Net-(D7-C)") (class "Default")
      (node (ref "D7") (pin "3") (pinfunction "C_3") (pintype "passive"))
      (node (ref "Q11") (pin "D") (pinfunction "D_D") (pintype "passive"))
      (node (ref "R59") (pin "2") (pinfunction "2_2") (pintype "passive"))
      (node (ref "SOV_5") (pin "1") (pinfunction "1_1") (pintype "passive"))
    )
    (net (code "30") (name "Net-(D8-A)") (class "Default")
      (node (ref "D8") (pin "1") (pinfunction "A_1") (pintype "passive"))
      (node (ref "R36") (pin "2") (pinfunction "2_2") (pintype "passive"))
    )
    (net (code "31") (name "Net-(D8-C)") (class "Default")
      (node (ref "D8") (pin "3") (pinfunction "C_3") (pintype "passive"))
      (node (ref "Q13") (pin "D") (pinfunction "D_D") (pintype "passive"))
      (node (ref "R62") (pin "2") (pinfunction "2_2") (pintype "passive"))
      (node (ref "SOV_6") (pin "1") (pinfunction "1_1") (pintype "passive"))
    )
    (net (code "32") (name "Net-(D9-A)") (class "Default")
      (node (ref "D9") (pin "1") (pinfunction "A_1") (pintype "passive"))
      (node (ref "R39") (pin "2") (pinfunction "2_2") (pintype "passive"))
    )
    (net (code "33") (name "Net-(D9-C)") (class "Default")
      (node (ref "D9") (pin "3") (pinfunction "C_3") (pintype "passive"))
      (node (ref "Q15") (pin "D") (pinfunction "D_D") (pintype "passive"))
      (node (ref "R63") (pin "2") (pinfunction "2_2") (pintype "passive"))
      (node (ref "SOV_7") (pin "1") (pinfunction "1_1") (pintype "passive"))
    )
    (net (code "34") (name "Net-(D10-A)") (class "Default")
      (node (ref "D10") (pin "1") (pinfunction "A_1") (pintype "passive"))
      (node (ref "R42") (pin "2") (pinfunction "2_2") (pintype "passive"))
    )
    (net (code "35") (name "Net-(D10-C)") (class "Default")
      (node (ref "D10") (pin "3") (pinfunction "C_3") (pintype "passive"))
      (node (ref "Q17") (pin "D") (pinfunction "D_D") (pintype "passive"))
      (node (ref "R19") (pin "2") (pinfunction "2_2") (pintype "passive"))
      (node (ref "SOV_8") (pin "1") (pinfunction "1_1") (pintype "passive"))
    )
    (net (code "36") (name "Net-(D11-A)") (class "Default")
      (node (ref "D11") (pin "1") (pinfunction "A_1") (pintype "passive"))
      (node (ref "R45") (pin "2") (pinfunction "2_2") (pintype "passive"))
    )
    (net (code "37") (name "Net-(D11-C)") (class "Default")
      (node (ref "D11") (pin "3") (pinfunction "C_3") (pintype "passive"))
      (node (ref "Q19") (pin "D") (pinfunction "D_D") (pintype "passive"))
      (node (ref "R20") (pin "2") (pinfunction "2_2") (pintype "passive"))
      (node (ref "SOV_9") (pin "1") (pinfunction "1_1") (pintype "passive"))
    )
    (net (code "38") (name "Net-(D13-A)") (class "Default")
      (node (ref "D13") (pin "1") (pinfunction "A_1") (pintype "passive"))
      (node (ref "R21") (pin "2") (pinfunction "2_2") (pintype "passive"))
    )
    (net (code "39") (name "Net-(D13-C)") (class "Default")
      (node (ref "D13") (pin "3") (pinfunction "C_3") (pintype "passive"))
      (node (ref "IGN") (pin "1") (pinfunction "1_1") (pintype "passive"))
      (node (ref "Q2") (pin "D") (pinfunction "D_D") (pintype "passive"))
      (node (ref "R17") (pin "2") (pinfunction "2_2") (pintype "passive"))
    )
    (net (code "40") (name "Net-(Q1-D)") (class "Default")
      (node (ref "Q1") (pin "3") (pinfunction "D_3") (pintype "bidirectional"))
      (node (ref "Q2") (pin "G") (pinfunction "G_G") (pintype "passive"))
      (node (ref "R6") (pin "1") (pinfunction "1_1") (pintype "passive"))
    )
    (net (code "41") (name "Net-(Q4-D)") (class "Default")
      (node (ref "Q3") (pin "G") (pinfunction "G_G") (pintype "passive"))
      (node (ref "Q4") (pin "3") (pinfunction "D_3") (pintype "bidirectional"))
      (node (ref "R2") (pin "1") (pinfunction "1_1") (pintype "passive"))
    )
    (net (code "42") (name "Net-(Q6-D)") (class "Default")
      (node (ref "Q5") (pin "G") (pinfunction "G_G") (pintype "passive"))
      (node (ref "Q6") (pin "3") (pinfunction "D_3") (pintype "bidirectional"))
      (node (ref "R22") (pin "1") (pinfunction "1_1") (pintype "passive"))
    )
    (net (code "43") (name "Net-(Q8-D)") (class "Default")
      (node (ref "Q7") (pin "G") (pinfunction "G_G") (pintype "passive"))
      (node (ref "Q8") (pin "3") (pinfunction "D_3") (pintype "bidirectional"))
      (node (ref "R25") (pin "1") (pinfunction "1_1") (pintype "passive"))
    )
    (net (code "44") (name "Net-(Q10-D)") (class "Default")
      (node (ref "Q10") (pin "3") (pinfunction "D_3") (pintype "bidirectional"))
      (node (ref "Q9") (pin "G") (pinfunction "G_G") (pintype "passive"))
      (node (ref "R28") (pin "1") (pinfunction "1_1") (pintype "passive"))
    )
    (net (code "45") (name "Net-(Q12-D)") (class "Default")
      (node (ref "Q11") (pin "G") (pinfunction "G_G") (pintype "passive"))
      (node (ref "Q12") (pin "3") (pinfunction "D_3") (pintype "bidirectional"))
      (node (ref "R31") (pin "1") (pinfunction "1_1") (pintype "passive"))
    )
    (net (code "46") (name "Net-(Q14-D)") (class "Default")
      (node (ref "Q13") (pin "G") (pinfunction "G_G") (pintype "passive"))
      (node (ref "Q14") (pin "3") (pinfunction "D_3") (pintype "bidirectional"))
      (node (ref "R34") (pin "1") (pinfunction "1_1") (pintype "passive"))
    )
    (net (code "47") (name "Net-(Q16-D)") (class "Default")
      (node (ref "Q15") (pin "G") (pinfunction "G_G") (pintype "passive"))
      (node (ref "Q16") (pin "3") (pinfunction "D_3") (pintype "bidirectional"))
      (node (ref "R37") (pin "1") (pinfunction "1_1") (pintype "passive"))
    )
    (net (code "48") (name "Net-(Q18-D)") (class "Default")
      (node (ref "Q17") (pin "G") (pinfunction "G_G") (pintype "passive"))
      (node (ref "Q18") (pin "3") (pinfunction "D_3") (pintype "bidirectional"))
      (node (ref "R40") (pin "1") (pinfunction "1_1") (pintype "passive"))
    )
    (net (code "49") (name "Net-(Q20-D)") (class "Default")
      (node (ref "Q19") (pin "G") (pinfunction "G_G") (pintype "passive"))
      (node (ref "Q20") (pin "3") (pinfunction "D_3") (pintype "bidirectional"))
      (node (ref "R43") (pin "1") (pinfunction "1_1") (pintype "passive"))
    )
    (net (code "50") (name "Net-(R17-Pad1)") (class "Default")
      (node (ref "R17") (pin "1") (pinfunction "1_1") (pintype "passive"))
      (node (ref "SOV_0.") (pin "A") (pinfunction "A_A") (pintype "passive"))
    )
    (net (code "51") (name "Net-(R18-Pad1)") (class "Default")
      (node (ref "R18") (pin "1") (pinfunction "1_1") (pintype "passive"))
      (node (ref "SOV_4.") (pin "A") (pinfunction "A_A") (pintype "passive"))
    )
    (net (code "52") (name "Net-(R19-Pad1)") (class "Default")
      (node (ref "R19") (pin "1") (pinfunction "1_1") (pintype "passive"))
      (node (ref "SOV_8.") (pin "A") (pinfunction "A_A") (pintype "passive"))
    )
    (net (code "53") (name "Net-(R20-Pad1)") (class "Default")
      (node (ref "R20") (pin "1") (pinfunction "1_1") (pintype "passive"))
      (node (ref "SOV_9.") (pin "A") (pinfunction "A_A") (pintype "passive"))
    )
    (net (code "54") (name "Net-(R59-Pad1)") (class "Default")
      (node (ref "R59") (pin "1") (pinfunction "1_1") (pintype "passive"))
      (node (ref "SOV_5.") (pin "A") (pinfunction "A_A") (pintype "passive"))
    )
    (net (code "55") (name "Net-(R60-Pad1)") (class "Default")
      (node (ref "R60") (pin "1") (pinfunction "1_1") (pintype "passive"))
      (node (ref "SOV_1.") (pin "A") (pinfunction "A_A") (pintype "passive"))
    )
    (net (code "56") (name "Net-(R61-Pad1)") (class "Default")
      (node (ref "R61") (pin "1") (pinfunction "1_1") (pintype "passive"))
      (node (ref "SOV_2.") (pin "A") (pinfunction "A_A") (pintype "passive"))
    )
    (net (code "57") (name "Net-(R62-Pad1)") (class "Default")
      (node (ref "R62") (pin "1") (pinfunction "1_1") (pintype "passive"))
      (node (ref "SOV_6.") (pin "A") (pinfunction "A_A") (pintype "passive"))
    )
    (net (code "58") (name "Net-(R63-Pad1)") (class "Default")
      (node (ref "R63") (pin "1") (pinfunction "1_1") (pintype "passive"))
      (node (ref "SOV_7.") (pin "A") (pinfunction "A_A") (pintype "passive"))
    )
    (net (code "59") (name "Net-(R64-Pad1)") (class "Default")
      (node (ref "R64") (pin "1") (pinfunction "1_1") (pintype "passive"))
      (node (ref "SOV_3.") (pin "A") (pinfunction "A_A") (pintype "passive"))
    )
    (net (code "60") (name "Net-(U$2-BST)") (class "Default")
      (node (ref "R81") (pin "1") (pinfunction "1_1") (pintype "passive"))
      (node (ref "U$2") (pin "P$1") (pinfunction "BST_P$1") (pintype "bidirectional"))
    )
    (net (code "61") (name "Net-(U$2-EN)") (class "Default")
      (node (ref "R76") (pin "1") (pinfunction "1_1") (pintype "passive"))
      (node (ref "R77") (pin "2") (pinfunction "2_2") (pintype "passive"))
      (node (ref "U$2") (pin "P$4") (pinfunction "EN_P$4") (pintype "input"))
    )
    (net (code "62") (name "Net-(U$2-FB)") (class "Default")
      (node (ref "C47") (pin "2") (pinfunction "2_2") (pintype "passive"))
      (node (ref "R69") (pin "1") (pinfunction "1_1") (pintype "passive"))
      (node (ref "R75") (pin "2") (pinfunction "2_2") (pintype "passive"))
      (node (ref "U$2") (pin "P$3") (pinfunction "FB_P$3") (pintype "bidirectional"))
    )
    (net (code "63") (name "Net-(U$2-SW)") (class "Default")
      (node (ref "C43") (pin "2") (pinfunction "2_2") (pintype "passive"))
      (node (ref "D31") (pin "C") (pinfunction "C_C") (pintype "passive"))
      (node (ref "L3") (pin "1") (pinfunction "1_1") (pintype "passive"))
      (node (ref "U$2") (pin "P$6") (pinfunction "SW_P$6") (pintype "bidirectional"))
    )
    (net (code "64") (name "PA_0") (class "Default")
      (node (ref "CN7") (pin "28") (pinfunction "28_28") (pintype "passive"))
    )
    (net (code "65") (name "PA_1") (class "Default")
      (node (ref "CN7") (pin "30") (pinfunction "30_30") (pintype "passive"))
    )
    (net (code "66") (name "PA_2") (class "Default")
      (node (ref "CN10") (pin "35") (pinfunction "35_35") (pintype "passive"))
    )
    (net (code "67") (name "PA_3") (class "Default")
      (node (ref "CN10") (pin "37") (pinfunction "37_37") (pintype "passive"))
    )
    (net (code "68") (name "PA_4") (class "Default")
      (node (ref "CN7") (pin "32") (pinfunction "32_32") (pintype "passive"))
    )
    (net (code "69") (name "PA_5") (class "Default")
      (node (ref "CN10") (pin "11") (pinfunction "11_11") (pintype "passive"))
    )
    (net (code "70") (name "PA_7") (class "Default")
      (node (ref "CN10") (pin "15") (pinfunction "15_15") (pintype "passive"))
    )
    (net (code "71") (name "PA_13") (class "Default")
      (node (ref "CN7") (pin "13") (pinfunction "13_13") (pintype "passive"))
    )
    (net (code "72") (name "PA_14") (class "Default")
      (node (ref "CN7") (pin "15") (pinfunction "15_15") (pintype "passive"))
    )
    (net (code "73") (name "PA_15") (class "Default")
      (node (ref "CN7") (pin "17") (pinfunction "17_17") (pintype "passive"))
    )
    (net (code "74") (name "PB_0") (class "Default")
      (node (ref "CN7") (pin "34") (pinfunction "34_34") (pintype "passive"))
    )
    (net (code "75") (name "PB_2") (class "Default")
      (node (ref "CN10") (pin "22") (pinfunction "22_22") (pintype "passive"))
    )
    (net (code "76") (name "PB_3") (class "Default")
      (node (ref "CN10") (pin "31") (pinfunction "31_31") (pintype "passive"))
    )
    (net (code "77") (name "PB_4") (class "Default")
      (node (ref "CN10") (pin "27") (pinfunction "27_27") (pintype "passive"))
    )
    (net (code "78") (name "PB_5") (class "Default")
      (node (ref "CN10") (pin "29") (pinfunction "29_29") (pintype "passive"))
    )
    (net (code "79") (name "PB_6") (class "Default")
      (node (ref "CN10") (pin "17") (pinfunction "17_17") (pintype "passive"))
    )
    (net (code "80") (name "PB_7") (class "Default")
      (node (ref "CN7") (pin "21") (pinfunction "21_21") (pintype "passive"))
    )
    (net (code "81") (name "PB_8") (class "Default")
      (node (ref "CN10") (pin "3") (pinfunction "3_3") (pintype "passive"))
    )
    (net (code "82") (name "PB_9") (class "Default")
      (node (ref "CN10") (pin "5") (pinfunction "5_5") (pintype "passive"))
    )
    (net (code "83") (name "PB_11") (class "Default")
      (node (ref "CN10") (pin "18") (pinfunction "18_18") (pintype "passive"))
    )
    (net (code "84") (name "PB_12") (class "Default")
      (node (ref "CN10") (pin "16") (pinfunction "16_16") (pintype "passive"))
    )
    (net (code "85") (name "PB_14") (class "Default")
      (node (ref "CN10") (pin "28") (pinfunction "28_28") (pintype "passive"))
    )
    (net (code "86") (name "PC_0") (class "Default")
      (node (ref "CN7") (pin "38") (pinfunction "38_38") (pintype "passive"))
    )
    (net (code "87") (name "PC_1") (class "Default")
      (node (ref "CN7") (pin "36") (pinfunction "36_36") (pintype "passive"))
    )
    (net (code "88") (name "PC_2") (class "Default")
      (node (ref "CN7") (pin "35") (pinfunction "35_35") (pintype "passive"))
    )
    (net (code "89") (name "PC_3") (class "Default")
      (node (ref "CN7") (pin "37") (pinfunction "37_37") (pintype "passive"))
    )
    (net (code "90") (name "PC_8") (class "Default")
      (node (ref "CN10") (pin "2") (pinfunction "2_2") (pintype "passive"))
    )
    (net (code "91") (name "PC_9") (class "Default")
      (node (ref "CN10") (pin "1") (pinfunction "1_1") (pintype "passive"))
    )
    (net (code "92") (name "PC_10") (class "Default")
      (node (ref "CN7") (pin "1") (pinfunction "1_1") (pintype "passive"))
    )
    (net (code "93") (name "PC_11") (class "Default")
      (node (ref "CN7") (pin "2") (pinfunction "2_2") (pintype "passive"))
    )
    (net (code "94") (name "PC_12") (class "Default")
      (node (ref "CN7") (pin "3") (pinfunction "3_3") (pintype "passive"))
    )
    (net (code "95") (name "PC_13") (class "Default")
      (node (ref "CN7") (pin "23") (pinfunction "23_23") (pintype "passive"))
    )
    (net (code "96") (name "PC_14") (class "Default")
      (node (ref "CN7") (pin "25") (pinfunction "25_25") (pintype "passive"))
    )
    (net (code "97") (name "PC_15") (class "Default")
      (node (ref "CN7") (pin "27") (pinfunction "27_27") (pintype "passive"))
    )
    (net (code "98") (name "PD_2") (class "Default")
      (node (ref "CN7") (pin "4") (pinfunction "4_4") (pintype "passive"))
    )
    (net (code "99") (name "PH_0") (class "Default")
      (node (ref "CN7") (pin "29") (pinfunction "29_29") (pintype "passive"))
    )
    (net (code "100") (name "PH_1") (class "Default")
      (node (ref "CN7") (pin "31") (pinfunction "31_31") (pintype "passive"))
    )
    (net (code "101") (name "RESET") (class "Default")
      (node (ref "CN7") (pin "14") (pinfunction "14_14") (pintype "passive"))
    )
    (net (code "102") (name "RTS_VI") (class "Default")
      (node (ref "CN10") (pin "24") (pinfunction "24_24") (pintype "passive"))
      (node (ref "JP1") (pin "5") (pinfunction "5_5") (pintype "passive"))
    )
    (net (code "103") (name "RX_VI") (class "Default")
      (node (ref "CN10") (pin "6") (pinfunction "6_6") (pintype "passive"))
      (node (ref "JP1") (pin "2") (pinfunction "2_2") (pintype "passive"))
    )
    (net (code "104") (name "SOL_GPIO_0") (class "Default")
      (node (ref "CN10") (pin "33") (pinfunction "33_33") (pintype "passive"))
      (node (ref "Q1") (pin "1") (pinfunction "G_1") (pintype "bidirectional"))
      (node (ref "R16") (pin "2") (pinfunction "2_2") (pintype "passive"))
    )
    (net (code "105") (name "SOL_GPIO_1") (class "Default")
      (node (ref "CN10") (pin "14") (pinfunction "14_14") (pintype "passive"))
      (node (ref "Q4") (pin "1") (pinfunction "G_1") (pintype "bidirectional"))
      (node (ref "R3") (pin "2") (pinfunction "2_2") (pintype "passive"))
    )
    (net (code "106") (name "SOL_GPIO_2") (class "Default")
      (node (ref "CN10") (pin "12") (pinfunction "12_12") (pintype "passive"))
      (node (ref "Q6") (pin "1") (pinfunction "G_1") (pintype "bidirectional"))
      (node (ref "R23") (pin "2") (pinfunction "2_2") (pintype "passive"))
    )
    (net (code "107") (name "SOL_GPIO_3") (class "Default")
      (node (ref "CN10") (pin "19") (pinfunction "19_19") (pintype "passive"))
      (node (ref "Q8") (pin "1") (pinfunction "G_1") (pintype "bidirectional"))
      (node (ref "R26") (pin "2") (pinfunction "2_2") (pintype "passive"))
    )
    (net (code "108") (name "SOL_GPIO_4") (class "Default")
      (node (ref "CN10") (pin "4") (pinfunction "4_4") (pintype "passive"))
      (node (ref "Q10") (pin "1") (pinfunction "G_1") (pintype "bidirectional"))
      (node (ref "R29") (pin "2") (pinfunction "2_2") (pintype "passive"))
    )
    (net (code "109") (name "SOL_GPIO_5") (class "Default")
      (node (ref "CN10") (pin "21") (pinfunction "21_21") (pintype "passive"))
      (node (ref "Q12") (pin "1") (pinfunction "G_1") (pintype "bidirectional"))
      (node (ref "R32") (pin "2") (pinfunction "2_2") (pintype "passive"))
    )
    (net (code "110") (name "SOL_GPIO_6") (class "Default")
      (node (ref "CN10") (pin "23") (pinfunction "23_23") (pintype "passive"))
      (node (ref "Q14") (pin "1") (pinfunction "G_1") (pintype "bidirectional"))
      (node (ref "R35") (pin "2") (pinfunction "2_2") (pintype "passive"))
    )
    (net (code "111") (name "SOL_GPIO_7") (class "Default")
      (node (ref "CN10") (pin "26") (pinfunction "26_26") (pintype "passive"))
      (node (ref "Q16") (pin "1") (pinfunction "G_1") (pintype "bidirectional"))
      (node (ref "R38") (pin "2") (pinfunction "2_2") (pintype "passive"))
    )
    (net (code "112") (name "SOL_GPIO_8") (class "Default")
      (node (ref "CN10") (pin "25") (pinfunction "25_25") (pintype "passive"))
      (node (ref "Q18") (pin "1") (pinfunction "G_1") (pintype "bidirectional"))
      (node (ref "R41") (pin "2") (pinfunction "2_2") (pintype "passive"))
    )
    (net (code "113") (name "SOL_GPIO_9") (class "Default")
      (node (ref "CN10") (pin "30") (pinfunction "30_30") (pintype "passive"))
      (node (ref "Q20") (pin "1") (pinfunction "G_1") (pintype "bidirectional"))
      (node (ref "R44") (pin "2") (pinfunction "2_2") (pintype "passive"))
    )
    (net (code "114") (name "TX_VI") (class "Default")
      (node (ref "CN10") (pin "34") (pinfunction "34_34") (pintype "passive"))
      (node (ref "JP1") (pin "1") (pinfunction "1_1") (pintype "passive"))
    )
    (net (code "115") (name "U5V") (class "Default")
      (node (ref "CN10") (pin "8") (pinfunction "8_8") (pintype "passive"))
    )
    (net (code "116") (name "V5_INPUT") (class "Default")
      (node (ref "CN7") (pin "18") (pinfunction "18_18") (pintype "passive"))
    )
    (net (code "117") (name "VBAT") (class "Default")
      (node (ref "CN7") (pin "33") (pinfunction "33_33") (pintype "passive"))
    )
    (net (code "118") (name "VBATT") (class "Default")
      (node (ref "BATTERY") (pin "1") (pinfunction "1_1") (pintype "passive"))
      (node (ref "C45") (pin "1") (pinfunction "1_1") (pintype "passive"))
      (node (ref "C46") (pin "1") (pinfunction "1_1") (pintype "passive"))
      (node (ref "Q11") (pin "S") (pinfunction "S_S") (pintype "passive"))
      (node (ref "Q13") (pin "S") (pinfunction "S_S") (pintype "passive"))
      (node (ref "Q15") (pin "S") (pinfunction "S_S") (pintype "passive"))
      (node (ref "Q17") (pin "S") (pinfunction "S_S") (pintype "passive"))
      (node (ref "Q19") (pin "S") (pinfunction "S_S") (pintype "passive"))
      (node (ref "Q2") (pin "S") (pinfunction "S_S") (pintype "passive"))
      (node (ref "Q3") (pin "S") (pinfunction "S_S") (pintype "passive"))
      (node (ref "Q5") (pin "S") (pinfunction "S_S") (pintype "passive"))
      (node (ref "Q7") (pin "S") (pinfunction "S_S") (pintype "passive"))
      (node (ref "R2") (pin "2") (pinfunction "2_2") (pintype "passive"))
      (node (ref "R22") (pin "2") (pinfunction "2_2") (pintype "passive"))
      (node (ref "R25") (pin "2") (pinfunction "2_2") (pintype "passive"))
      (node (ref "R31") (pin "2") (pinfunction "2_2") (pintype "passive"))
      (node (ref "R34") (pin "2") (pinfunction "2_2") (pintype "passive"))
      (node (ref "R37") (pin "2") (pinfunction "2_2") (pintype "passive"))
      (node (ref "R40") (pin "2") (pinfunction "2_2") (pintype "passive"))
      (node (ref "R43") (pin "2") (pinfunction "2_2") (pintype "passive"))
      (node (ref "R6") (pin "2") (pinfunction "2_2") (pintype "passive"))
      (node (ref "R76") (pin "2") (pinfunction "2_2") (pintype "passive"))
      (node (ref "U$2") (pin "P$5") (pinfunction "IN_P$5") (pintype "power_in"))
    )
    (net (code "119") (name "VDD") (class "Default")
      (node (ref "CN7") (pin "5") (pinfunction "5_5") (pintype "passive"))
    )
    (net (code "120") (name "VIN") (class "Default")
      (node (ref "CN7") (pin "24") (pinfunction "24_24") (pintype "passive"))
    )
  )
)
